# placa_v1.net
KiCad netlist of a schematic drawn in EAGLE
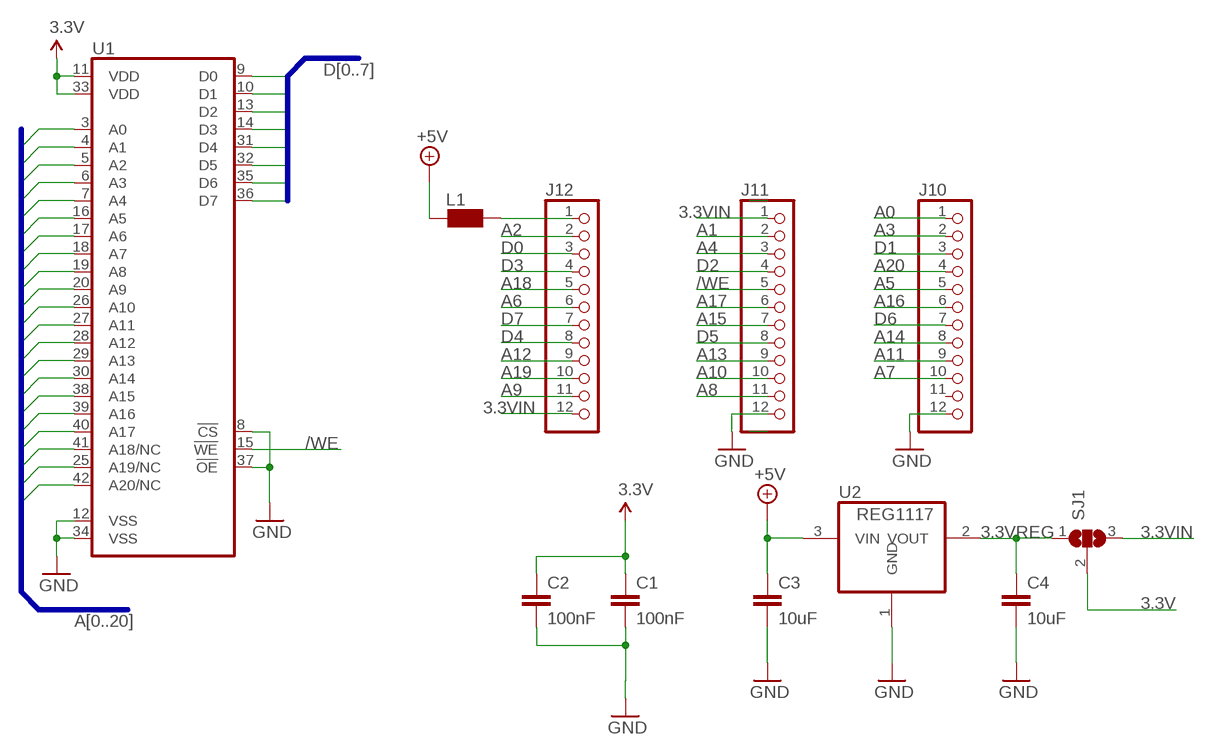
[diagram p0: schematic, sheet 1]

(export (version "E")
  (design (tool "Eeschema 10.0.6"))
  (components
    (comp (ref "C1")
      (value "100nF")
      (footprint "eagle-import:C0805K")
      (libsource (lib "eagle-import") (part "C-EUC0805K"))
    )
    (comp (ref "C2")
      (value "100nF")
      (footprint "eagle-import:C0805K")
      (libsource (lib "eagle-import") (part "C-EUC0805K"))
    )
    (comp (ref "C3")
      (value "10uF")
      (footprint "eagle-import:C0805K")
      (libsource (lib "eagle-import") (part "C-EUC0805K"))
    )
    (comp (ref "C4")
      (value "10uF")
      (footprint "eagle-import:C0805K")
      (libsource (lib "eagle-import") (part "C-EUC0805K"))
    )
    (comp (ref "J10")
      (value "PINHD-1X12")
      (footprint "eagle-import:1X12")
      (libsource (lib "eagle-import") (part "PINHD-1X12"))
    )
    (comp (ref "J11")
      (value "PINHD-1X12")
      (footprint "eagle-import:1X12")
      (libsource (lib "eagle-import") (part "PINHD-1X12"))
    )
    (comp (ref "J12")
      (value "PINHD-1X12")
      (footprint "eagle-import:1X12")
      (libsource (lib "eagle-import") (part "PINHD-1X12"))
    )
    (comp (ref "L1")
      (value "WE-CBF_0805")
      (footprint "eagle-import:0805")
      (libsource (lib "eagle-import") (part "WE-CBF_0805"))
    )
    (comp (ref "SJ1")
      (value "SJ2W")
      (footprint "eagle-import:SJ_2")
      (libsource (lib "eagle-import") (part "SJ2W"))
    )
    (comp (ref "U1")
      (value "ISSI_SRAM_8BIT")
      (footprint "eagle-import:TSOP44-II")
      (libsource (lib "eagle-import") (part "ISSI_SRAM_8BIT"))
    )
    (comp (ref "U2")
      (value "REG1117")
      (footprint "eagle-import:SOT223")
      (libsource (lib "eagle-import") (part "REG1117"))
    )
  )
  (nets
    (net (code "1") (name "+5V") (class "Default")
      (node (ref "C3") (pin "1") (pinfunction "1_1") (pintype "passive"))
      (node (ref "L1") (pin "2") (pinfunction "2_2") (pintype "passive"))
      (node (ref "U2") (pin "3") (pinfunction "VIN_3") (pintype "input"))
    )
    (net (code "2") (name "/3.3VIN") (class "Default")
      (node (ref "J11") (pin "1") (pinfunction "1_1") (pintype "passive"))
      (node (ref "J12") (pin "12") (pinfunction "12_12") (pintype "passive"))
      (node (ref "SJ1") (pin "3") (pinfunction "3_3") (pintype "passive"))
    )
    (net (code "3") (name "/3.3VREG") (class "Default")
      (node (ref "C4") (pin "1") (pinfunction "1_1") (pintype "passive"))
      (node (ref "SJ1") (pin "1") (pinfunction "1_1") (pintype "passive"))
      (node (ref "U2") (pin "2") (pinfunction "VOUT_2") (pintype "output"))
    )
    (net (code "4") (name "/A0") (class "Default")
      (node (ref "J10") (pin "1") (pinfunction "1_1") (pintype "passive"))
      (node (ref "U1") (pin "3") (pinfunction "A0_3") (pintype "input"))
    )
    (net (code "5") (name "/A1") (class "Default")
      (node (ref "J11") (pin "2") (pinfunction "2_2") (pintype "passive"))
      (node (ref "U1") (pin "4") (pinfunction "A1_4") (pintype "input"))
    )
    (net (code "6") (name "/A2") (class "Default")
      (node (ref "J12") (pin "2") (pinfunction "2_2") (pintype "passive"))
      (node (ref "U1") (pin "5") (pinfunction "A2_5") (pintype "input"))
    )
    (net (code "7") (name "/A3") (class "Default")
      (node (ref "J10") (pin "2") (pinfunction "2_2") (pintype "passive"))
      (node (ref "U1") (pin "6") (pinfunction "A3_6") (pintype "input"))
    )
    (net (code "8") (name "/A4") (class "Default")
      (node (ref "J11") (pin "3") (pinfunction "3_3") (pintype "passive"))
      (node (ref "U1") (pin "7") (pinfunction "A4_7") (pintype "input"))
    )
    (net (code "9") (name "/A5") (class "Default")
      (node (ref "J10") (pin "5") (pinfunction "5_5") (pintype "passive"))
      (node (ref "U1") (pin "16") (pinfunction "A5_16") (pintype "input"))
    )
    (net (code "10") (name "/A6") (class "Default")
      (node (ref "J12") (pin "6") (pinfunction "6_6") (pintype "passive"))
      (node (ref "U1") (pin "17") (pinfunction "A6_17") (pintype "input"))
    )
    (net (code "11") (name "/A7") (class "Default")
      (node (ref "J10") (pin "10") (pinfunction "10_10") (pintype "passive"))
      (node (ref "U1") (pin "18") (pinfunction "A7_18") (pintype "input"))
    )
    (net (code "12") (name "/A8") (class "Default")
      (node (ref "J11") (pin "11") (pinfunction "11_11") (pintype "passive"))
      (node (ref "U1") (pin "19") (pinfunction "A8_19") (pintype "input"))
    )
    (net (code "13") (name "/A9") (class "Default")
      (node (ref "J12") (pin "11") (pinfunction "11_11") (pintype "passive"))
      (node (ref "U1") (pin "20") (pinfunction "A9_20") (pintype "input"))
    )
    (net (code "14") (name "/A10") (class "Default")
      (node (ref "J11") (pin "10") (pinfunction "10_10") (pintype "passive"))
      (node (ref "U1") (pin "26") (pinfunction "A10_26") (pintype "input"))
    )
    (net (code "15") (name "/A11") (class "Default")
      (node (ref "J10") (pin "9") (pinfunction "9_9") (pintype "passive"))
      (node (ref "U1") (pin "27") (pinfunction "A11_27") (pintype "input"))
    )
    (net (code "16") (name "/A12") (class "Default")
      (node (ref "J12") (pin "9") (pinfunction "9_9") (pintype "passive"))
      (node (ref "U1") (pin "28") (pinfunction "A12_28") (pintype "input"))
    )
    (net (code "17") (name "/A13") (class "Default")
      (node (ref "J11") (pin "9") (pinfunction "9_9") (pintype "passive"))
      (node (ref "U1") (pin "29") (pinfunction "A13_29") (pintype "input"))
    )
    (net (code "18") (name "/A14") (class "Default")
      (node (ref "J10") (pin "8") (pinfunction "8_8") (pintype "passive"))
      (node (ref "U1") (pin "30") (pinfunction "A14_30") (pintype "input"))
    )
    (net (code "19") (name "/A15") (class "Default")
      (node (ref "J11") (pin "7") (pinfunction "7_7") (pintype "passive"))
      (node (ref "U1") (pin "38") (pinfunction "A15_38") (pintype "input"))
    )
    (net (code "20") (name "/A16") (class "Default")
      (node (ref "J10") (pin "6") (pinfunction "6_6") (pintype "passive"))
      (node (ref "U1") (pin "39") (pinfunction "A16_39") (pintype "input"))
    )
    (net (code "21") (name "/A17") (class "Default")
      (node (ref "J11") (pin "6") (pinfunction "6_6") (pintype "passive"))
      (node (ref "U1") (pin "40") (pinfunction "A17_40") (pintype "input"))
    )
    (net (code "22") (name "/A18") (class "Default")
      (node (ref "J12") (pin "5") (pinfunction "5_5") (pintype "passive"))
      (node (ref "U1") (pin "41") (pinfunction "A18/NC_41") (pintype "input"))
    )
    (net (code "23") (name "/A19") (class "Default")
      (node (ref "J12") (pin "10") (pinfunction "10_10") (pintype "passive"))
      (node (ref "U1") (pin "25") (pinfunction "A19/NC_25") (pintype "input"))
    )
    (net (code "24") (name "/A20") (class "Default")
      (node (ref "J10") (pin "4") (pinfunction "4_4") (pintype "passive"))
      (node (ref "U1") (pin "42") (pinfunction "A20/NC_42") (pintype "input"))
    )
    (net (code "26") (name "/D0") (class "Default")
      (node (ref "J12") (pin "3") (pinfunction "3_3") (pintype "passive"))
      (node (ref "U1") (pin "9") (pinfunction "D0_9") (pintype "bidirectional"))
    )
    (net (code "27") (name "/D1") (class "Default")
      (node (ref "J10") (pin "3") (pinfunction "3_3") (pintype "passive"))
      (node (ref "U1") (pin "10") (pinfunction "D1_10") (pintype "bidirectional"))
    )
    (net (code "28") (name "/D2") (class "Default")
      (node (ref "J11") (pin "4") (pinfunction "4_4") (pintype "passive"))
      (node (ref "U1") (pin "13") (pinfunction "D2_13") (pintype "bidirectional"))
    )
    (net (code "29") (name "/D3") (class "Default")
      (node (ref "J12") (pin "4") (pinfunction "4_4") (pintype "passive"))
      (node (ref "U1") (pin "14") (pinfunction "D3_14") (pintype "bidirectional"))
    )
    (net (code "30") (name "/D4") (class "Default")
      (node (ref "J12") (pin "8") (pinfunction "8_8") (pintype "passive"))
      (node (ref "U1") (pin "31") (pinfunction "D4_31") (pintype "bidirectional"))
    )
    (net (code "31") (name "/D5") (class "Default")
      (node (ref "J11") (pin "8") (pinfunction "8_8") (pintype "passive"))
      (node (ref "U1") (pin "32") (pinfunction "D5_32") (pintype "bidirectional"))
    )
    (net (code "32") (name "/D6") (class "Default")
      (node (ref "J10") (pin "7") (pinfunction "7_7") (pintype "passive"))
      (node (ref "U1") (pin "35") (pinfunction "D6_35") (pintype "bidirectional"))
    )
    (net (code "33") (name "/D7") (class "Default")
      (node (ref "J12") (pin "7") (pinfunction "7_7") (pintype "passive"))
      (node (ref "U1") (pin "36") (pinfunction "D7_36") (pintype "bidirectional"))
    )
    (net (code "35") (name "/{slash}WE") (class "Default")
      (node (ref "J11") (pin "5") (pinfunction "5_5") (pintype "passive"))
      (node (ref "U1") (pin "15") (pinfunction "~{WE}_15") (pintype "input"))
    )
    (net (code "36") (name "3.3V") (class "Default")
      (node (ref "C1") (pin "1") (pinfunction "1_1") (pintype "passive"))
      (node (ref "C2") (pin "1") (pinfunction "1_1") (pintype "passive"))
      (node (ref "SJ1") (pin "2") (pinfunction "2_2") (pintype "passive"))
      (node (ref "U1") (pin "11") (pinfunction "VDD_11") (pintype "input"))
      (node (ref "U1") (pin "33") (pinfunction "VDD_33") (pintype "input"))
    )
    (net (code "37") (name "GND") (class "Default")
      (node (ref "C1") (pin "2") (pinfunction "2_2") (pintype "passive"))
      (node (ref "C2") (pin "2") (pinfunction "2_2") (pintype "passive"))
      (node (ref "C3") (pin "2") (pinfunction "2_2") (pintype "passive"))
      (node (ref "C4") (pin "2") (pinfunction "2_2") (pintype "passive"))
      (node (ref "J10") (pin "12") (pinfunction "12_12") (pintype "passive"))
      (node (ref "J11") (pin "12") (pinfunction "12_12") (pintype "passive"))
      (node (ref "U1") (pin "12") (pinfunction "VSS_12") (pintype "input"))
      (node (ref "U1") (pin "34") (pinfunction "VSS_34") (pintype "input"))
      (node (ref "U1") (pin "37") (pinfunction "~{OE}_37") (pintype "input"))
      (node (ref "U1") (pin "8") (pinfunction "~{CS}_8") (pintype "input"))
      (node (ref "U2") (pin "1") (pinfunction "GND_1") (pintype "power_in"))
    )
    (net (code "38") (name "Net-(J12-Pad1)") (class "Default")
      (node (ref "J12") (pin "1") (pinfunction "1_1") (pintype "passive"))
      (node (ref "L1") (pin "1") (pinfunction "1_1") (pintype "passive"))
    )
    (net (code "39") (name "unconnected-(J10-Pad11)") (class "Default")
      (node (ref "J10") (pin "11") (pinfunction "11_11") (pintype "passive"))
    )
  )
)
